# music_51.net
KiCad netlist of a schematic drawn in Altium Designer
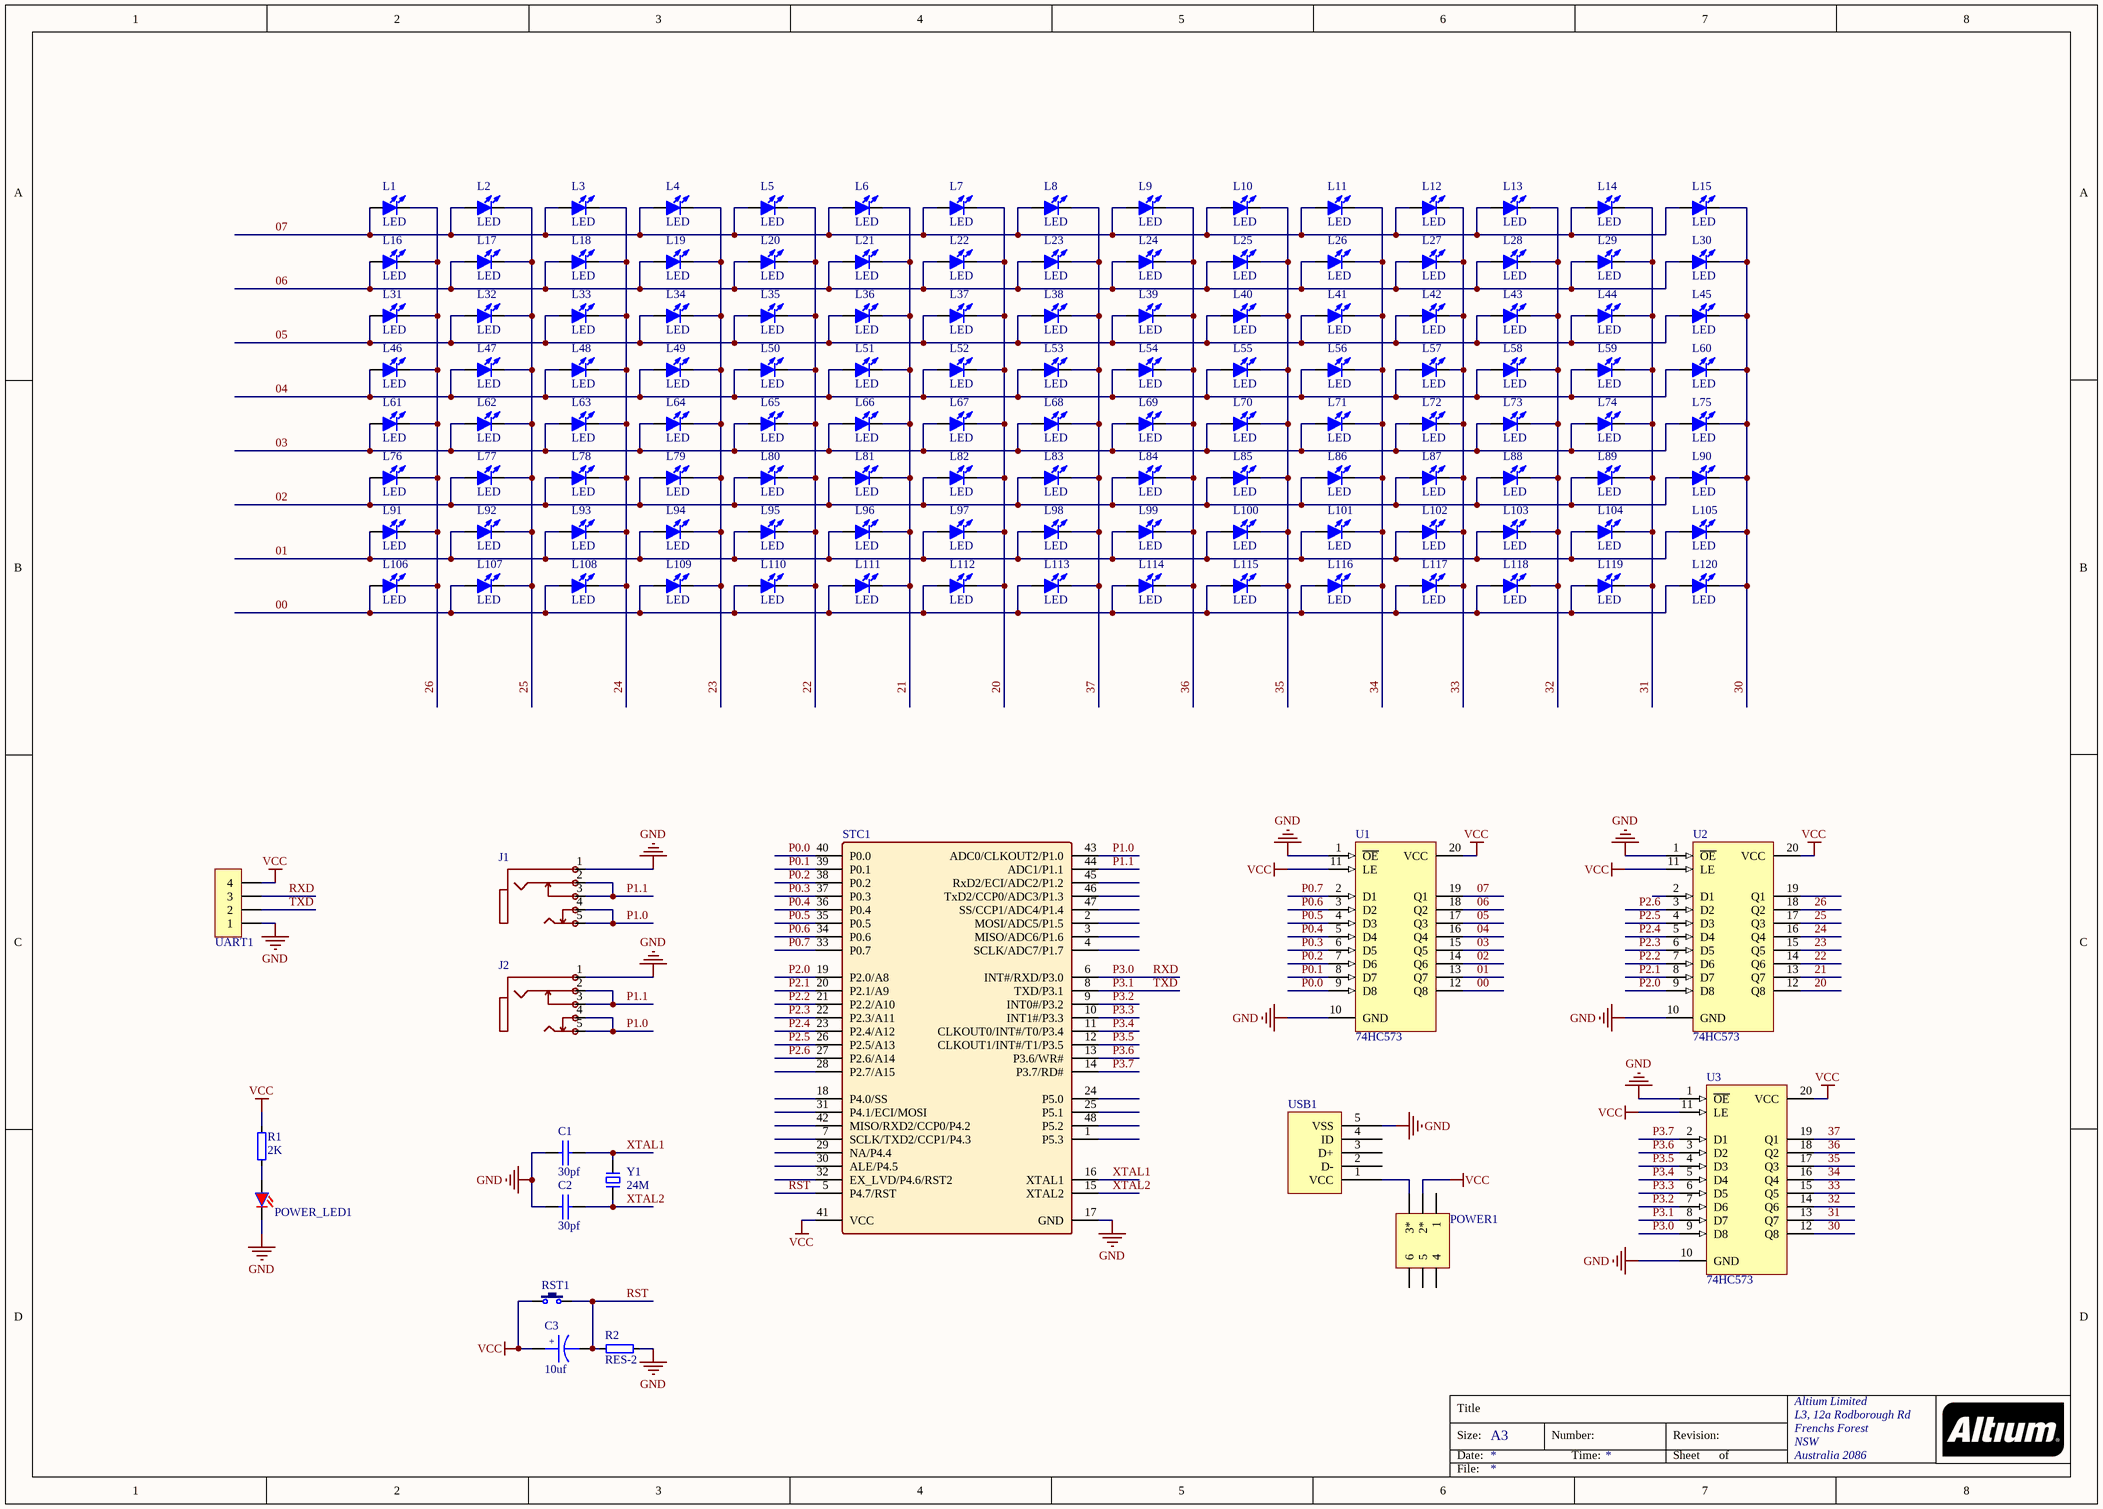
[diagram p0: music_51.SchDoc]

(export (version "E")
  (design (tool "Eeschema 10.0.6"))
  (components
    (comp (ref "C1") (value "30pf") (footprint "CAP-0805") (libsource (lib "Mylib_SCH") (part "Cap")))
    (comp (ref "C2") (value "30pf") (footprint "CAP-0805") (libsource (lib "Mylib_SCH") (part "Cap")))
    (comp (ref "C3") (value "10uf") (footprint "CAP-0805") (libsource (lib "Mylib_SCH") (part "Cap3+")))
    (comp (ref "J1") (value "PJ-307C") (footprint "PJ-307C") (libsource (lib "Mylib_SCH") (part "PJ-307C")))
    (comp (ref "J2") (value "PJ-307C") (footprint "PJ-307C") (libsource (lib "Mylib_SCH") (part "PJ-307C")))
    (comp (ref "L1") (value "LED") (footprint "LED") (libsource (lib "Mylib_SCH") (part "LED")))
    (comp (ref "L2") (value "LED") (footprint "LED") (libsource (lib "Mylib_SCH") (part "LED")))
    (comp (ref "L3") (value "LED") (footprint "LED") (libsource (lib "Mylib_SCH") (part "LED")))
    (comp (ref "L4") (value "LED") (footprint "LED") (libsource (lib "Mylib_SCH") (part "LED")))
    (comp (ref "L5") (value "LED") (footprint "LED") (libsource (lib "Mylib_SCH") (part "LED")))
    (comp (ref "L6") (value "LED") (footprint "LED") (libsource (lib "Mylib_SCH") (part "LED")))
    (comp (ref "L7") (value "LED") (footprint "LED") (libsource (lib "Mylib_SCH") (part "LED")))
    (comp (ref "L8") (value "LED") (footprint "LED") (libsource (lib "Mylib_SCH") (part "LED")))
    (comp (ref "L9") (value "LED") (footprint "LED") (libsource (lib "Mylib_SCH") (part "LED")))
    (comp (ref "L10") (value "LED") (footprint "LED") (libsource (lib "Mylib_SCH") (part "LED")))
    (comp (ref "L11") (value "LED") (footprint "LED") (libsource (lib "Mylib_SCH") (part "LED")))
    (comp (ref "L12") (value "LED") (footprint "LED") (libsource (lib "Mylib_SCH") (part "LED")))
    (comp (ref "L13") (value "LED") (footprint "LED") (libsource (lib "Mylib_SCH") (part "LED")))
    (comp (ref "L14") (value "LED") (footprint "LED") (libsource (lib "Mylib_SCH") (part "LED")))
    (comp (ref "L15") (value "LED") (footprint "LED") (libsource (lib "Mylib_SCH") (part "LED")))
    (comp (ref "L16") (value "LED") (footprint "LED") (libsource (lib "Mylib_SCH") (part "LED")))
    (comp (ref "L17") (value "LED") (footprint "LED") (libsource (lib "Mylib_SCH") (part "LED")))
    (comp (ref "L18") (value "LED") (footprint "LED") (libsource (lib "Mylib_SCH") (part "LED")))
    (comp (ref "L19") (value "LED") (footprint "LED") (libsource (lib "Mylib_SCH") (part "LED")))
    (comp (ref "L20") (value "LED") (footprint "LED") (libsource (lib "Mylib_SCH") (part "LED")))
    (comp (ref "L21") (value "LED") (footprint "LED") (libsource (lib "Mylib_SCH") (part "LED")))
    (comp (ref "L22") (value "LED") (footprint "LED") (libsource (lib "Mylib_SCH") (part "LED")))
    (comp (ref "L23") (value "LED") (footprint "LED") (libsource (lib "Mylib_SCH") (part "LED")))
    (comp (ref "L24") (value "LED") (footprint "LED") (libsource (lib "Mylib_SCH") (part "LED")))
    (comp (ref "L25") (value "LED") (footprint "LED") (libsource (lib "Mylib_SCH") (part "LED")))
    (comp (ref "L26") (value "LED") (footprint "LED") (libsource (lib "Mylib_SCH") (part "LED")))
    (comp (ref "L27") (value "LED") (footprint "LED") (libsource (lib "Mylib_SCH") (part "LED")))
    (comp (ref "L28") (value "LED") (footprint "LED") (libsource (lib "Mylib_SCH") (part "LED")))
    (comp (ref "L29") (value "LED") (footprint "LED") (libsource (lib "Mylib_SCH") (part "LED")))
    (comp (ref "L30") (value "LED") (footprint "LED") (libsource (lib "Mylib_SCH") (part "LED")))
    (comp (ref "L31") (value "LED") (footprint "LED") (libsource (lib "Mylib_SCH") (part "LED")))
    (comp (ref "L32") (value "LED") (footprint "LED") (libsource (lib "Mylib_SCH") (part "LED")))
    (comp (ref "L33") (value "LED") (footprint "LED") (libsource (lib "Mylib_SCH") (part "LED")))
    (comp (ref "L34") (value "LED") (footprint "LED") (libsource (lib "Mylib_SCH") (part "LED")))
    (comp (ref "L35") (value "LED") (footprint "LED") (libsource (lib "Mylib_SCH") (part "LED")))
    (comp (ref "L36") (value "LED") (footprint "LED") (libsource (lib "Mylib_SCH") (part "LED")))
    (comp (ref "L37") (value "LED") (footprint "LED") (libsource (lib "Mylib_SCH") (part "LED")))
    (comp (ref "L38") (value "LED") (footprint "LED") (libsource (lib "Mylib_SCH") (part "LED")))
    (comp (ref "L39") (value "LED") (footprint "LED") (libsource (lib "Mylib_SCH") (part "LED")))
    (comp (ref "L40") (value "LED") (footprint "LED") (libsource (lib "Mylib_SCH") (part "LED")))
    (comp (ref "L41") (value "LED") (footprint "LED") (libsource (lib "Mylib_SCH") (part "LED")))
    (comp (ref "L42") (value "LED") (footprint "LED") (libsource (lib "Mylib_SCH") (part "LED")))
    (comp (ref "L43") (value "LED") (footprint "LED") (libsource (lib "Mylib_SCH") (part "LED")))
    (comp (ref "L44") (value "LED") (footprint "LED") (libsource (lib "Mylib_SCH") (part "LED")))
    (comp (ref "L45") (value "LED") (footprint "LED") (libsource (lib "Mylib_SCH") (part "LED")))
    (comp (ref "L46") (value "LED") (footprint "LED") (libsource (lib "Mylib_SCH") (part "LED")))
    (comp (ref "L47") (value "LED") (footprint "LED") (libsource (lib "Mylib_SCH") (part "LED")))
    (comp (ref "L48") (value "LED") (footprint "LED") (libsource (lib "Mylib_SCH") (part "LED")))
    (comp (ref "L49") (value "LED") (footprint "LED") (libsource (lib "Mylib_SCH") (part "LED")))
    (comp (ref "L50") (value "LED") (footprint "LED") (libsource (lib "Mylib_SCH") (part "LED")))
    (comp (ref "L51") (value "LED") (footprint "LED") (libsource (lib "Mylib_SCH") (part "LED")))
    (comp (ref "L52") (value "LED") (footprint "LED") (libsource (lib "Mylib_SCH") (part "LED")))
    (comp (ref "L53") (value "LED") (footprint "LED") (libsource (lib "Mylib_SCH") (part "LED")))
    (comp (ref "L54") (value "LED") (footprint "LED") (libsource (lib "Mylib_SCH") (part "LED")))
    (comp (ref "L55") (value "LED") (footprint "LED") (libsource (lib "Mylib_SCH") (part "LED")))
    (comp (ref "L56") (value "LED") (footprint "LED") (libsource (lib "Mylib_SCH") (part "LED")))
    (comp (ref "L57") (value "LED") (footprint "LED") (libsource (lib "Mylib_SCH") (part "LED")))
    (comp (ref "L58") (value "LED") (footprint "LED") (libsource (lib "Mylib_SCH") (part "LED")))
    (comp (ref "L59") (value "LED") (footprint "LED") (libsource (lib "Mylib_SCH") (part "LED")))
    (comp (ref "L60") (value "LED") (footprint "LED") (libsource (lib "Mylib_SCH") (part "LED")))
    (comp (ref "L61") (value "LED") (footprint "LED") (libsource (lib "Mylib_SCH") (part "LED")))
    (comp (ref "L62") (value "LED") (footprint "LED") (libsource (lib "Mylib_SCH") (part "LED")))
    (comp (ref "L63") (value "LED") (footprint "LED") (libsource (lib "Mylib_SCH") (part "LED")))
    (comp (ref "L64") (value "LED") (footprint "LED") (libsource (lib "Mylib_SCH") (part "LED")))
    (comp (ref "L65") (value "LED") (footprint "LED") (libsource (lib "Mylib_SCH") (part "LED")))
    (comp (ref "L66") (value "LED") (footprint "LED") (libsource (lib "Mylib_SCH") (part "LED")))
    (comp (ref "L67") (value "LED") (footprint "LED") (libsource (lib "Mylib_SCH") (part "LED")))
    (comp (ref "L68") (value "LED") (footprint "LED") (libsource (lib "Mylib_SCH") (part "LED")))
    (comp (ref "L69") (value "LED") (footprint "LED") (libsource (lib "Mylib_SCH") (part "LED")))
    (comp (ref "L70") (value "LED") (footprint "LED") (libsource (lib "Mylib_SCH") (part "LED")))
    (comp (ref "L71") (value "LED") (footprint "LED") (libsource (lib "Mylib_SCH") (part "LED")))
    (comp (ref "L72") (value "LED") (footprint "LED") (libsource (lib "Mylib_SCH") (part "LED")))
    (comp (ref "L73") (value "LED") (footprint "LED") (libsource (lib "Mylib_SCH") (part "LED")))
    (comp (ref "L74") (value "LED") (footprint "LED") (libsource (lib "Mylib_SCH") (part "LED")))
    (comp (ref "L75") (value "LED") (footprint "LED") (libsource (lib "Mylib_SCH") (part "LED")))
    (comp (ref "L76") (value "LED") (footprint "LED") (libsource (lib "Mylib_SCH") (part "LED")))
    (comp (ref "L77") (value "LED") (footprint "LED") (libsource (lib "Mylib_SCH") (part "LED")))
    (comp (ref "L78") (value "LED") (footprint "LED") (libsource (lib "Mylib_SCH") (part "LED")))
    (comp (ref "L79") (value "LED") (footprint "LED") (libsource (lib "Mylib_SCH") (part "LED")))
    (comp (ref "L80") (value "LED") (footprint "LED") (libsource (lib "Mylib_SCH") (part "LED")))
    (comp (ref "L81") (value "LED") (footprint "LED") (libsource (lib "Mylib_SCH") (part "LED")))
    (comp (ref "L82") (value "LED") (footprint "LED") (libsource (lib "Mylib_SCH") (part "LED")))
    (comp (ref "L83") (value "LED") (footprint "LED") (libsource (lib "Mylib_SCH") (part "LED")))
    (comp (ref "L84") (value "LED") (footprint "LED") (libsource (lib "Mylib_SCH") (part "LED")))
    (comp (ref "L85") (value "LED") (footprint "LED") (libsource (lib "Mylib_SCH") (part "LED")))
    (comp (ref "L86") (value "LED") (footprint "LED") (libsource (lib "Mylib_SCH") (part "LED")))
    (comp (ref "L87") (value "LED") (footprint "LED") (libsource (lib "Mylib_SCH") (part "LED")))
    (comp (ref "L88") (value "LED") (footprint "LED") (libsource (lib "Mylib_SCH") (part "LED")))
    (comp (ref "L89") (value "LED") (footprint "LED") (libsource (lib "Mylib_SCH") (part "LED")))
    (comp (ref "L90") (value "LED") (footprint "LED") (libsource (lib "Mylib_SCH") (part "LED")))
    (comp (ref "L91") (value "LED") (footprint "LED") (libsource (lib "Mylib_SCH") (part "LED")))
    (comp (ref "L92") (value "LED") (footprint "LED") (libsource (lib "Mylib_SCH") (part "LED")))
    (comp (ref "L93") (value "LED") (footprint "LED") (libsource (lib "Mylib_SCH") (part "LED")))
    (comp (ref "L94") (value "LED") (footprint "LED") (libsource (lib "Mylib_SCH") (part "LED")))
    (comp (ref "L95") (value "LED") (footprint "LED") (libsource (lib "Mylib_SCH") (part "LED")))
    (comp (ref "L96") (value "LED") (footprint "LED") (libsource (lib "Mylib_SCH") (part "LED")))
    (comp (ref "L97") (value "LED") (footprint "LED") (libsource (lib "Mylib_SCH") (part "LED")))
    (comp (ref "L98") (value "LED") (footprint "LED") (libsource (lib "Mylib_SCH") (part "LED")))
    (comp (ref "L99") (value "LED") (footprint "LED") (libsource (lib "Mylib_SCH") (part "LED")))
    (comp (ref "L100") (value "LED") (footprint "LED") (libsource (lib "Mylib_SCH") (part "LED")))
    (comp (ref "L101") (value "LED") (footprint "LED") (libsource (lib "Mylib_SCH") (part "LED")))
    (comp (ref "L102") (value "LED") (footprint "LED") (libsource (lib "Mylib_SCH") (part "LED")))
    (comp (ref "L103") (value "LED") (footprint "LED") (libsource (lib "Mylib_SCH") (part "LED")))
    (comp (ref "L104") (value "LED") (footprint "LED") (libsource (lib "Mylib_SCH") (part "LED")))
    (comp (ref "L105") (value "LED") (footprint "LED") (libsource (lib "Mylib_SCH") (part "LED")))
    (comp (ref "L106") (value "LED") (footprint "LED") (libsource (lib "Mylib_SCH") (part "LED")))
    (comp (ref "L107") (value "LED") (footprint "LED") (libsource (lib "Mylib_SCH") (part "LED")))
    (comp (ref "L108") (value "LED") (footprint "LED") (libsource (lib "Mylib_SCH") (part "LED")))
    (comp (ref "L109") (value "LED") (footprint "LED") (libsource (lib "Mylib_SCH") (part "LED")))
    (comp (ref "L110") (value "LED") (footprint "LED") (libsource (lib "Mylib_SCH") (part "LED")))
    (comp (ref "L111") (value "LED") (footprint "LED") (libsource (lib "Mylib_SCH") (part "LED")))
    (comp (ref "L112") (value "LED") (footprint "LED") (libsource (lib "Mylib_SCH") (part "LED")))
    (comp (ref "L113") (value "LED") (footprint "LED") (libsource (lib "Mylib_SCH") (part "LED")))
    (comp (ref "L114") (value "LED") (footprint "LED") (libsource (lib "Mylib_SCH") (part "LED")))
    (comp (ref "L115") (value "LED") (footprint "LED") (libsource (lib "Mylib_SCH") (part "LED")))
    (comp (ref "L116") (value "LED") (footprint "LED") (libsource (lib "Mylib_SCH") (part "LED")))
    (comp (ref "L117") (value "LED") (footprint "LED") (libsource (lib "Mylib_SCH") (part "LED")))
    (comp (ref "L118") (value "LED") (footprint "LED") (libsource (lib "Mylib_SCH") (part "LED")))
    (comp (ref "L119") (value "LED") (footprint "LED") (libsource (lib "Mylib_SCH") (part "LED")))
    (comp (ref "L120") (value "LED") (footprint "LED") (libsource (lib "Mylib_SCH") (part "LED")))
    (comp (ref "POWER1") (value "SWITCH") (footprint "KEY6") (libsource (lib "My51Lib") (part "SWITCH")))
    (comp (ref "POWER_LED1")
      (value "LED_Red")
      (footprint "LED")
      (libsource (lib "Mylib_SCH") (part "LED_Red"))
    )
    (comp (ref "R1") (value "2K") (footprint "RES-S0805") (libsource (lib "Mylib_SCH") (part "RES-2")))
    (comp (ref "R2") (value "RES-2") (footprint "RES-S0805") (libsource (lib "Mylib_SCH") (part "RES-2")))
    (comp (ref "RST1") (value "Key") (footprint "KEY4") (libsource (lib "Mylib_SCH") (part "Key")))
    (comp (ref "STC1")
      (value "STC12C5A60S2")
      (footprint "LQPF48_7*7")
      (libsource (lib "Mylib_SCH") (part "STC12C5A60S2"))
    )
    (comp (ref "U1") (value "74HC573") (footprint "SOIC-20") (libsource (lib "Mylib_SCH") (part "74HC573")))
    (comp (ref "U2") (value "74HC573") (footprint "SOIC-20") (libsource (lib "Mylib_SCH") (part "74HC573")))
    (comp (ref "U3") (value "74HC573") (footprint "SOIC-20") (libsource (lib "Mylib_SCH") (part "74HC573")))
    (comp (ref "UART1")
      (value "Header 1*4")
      (footprint "Header 1*4")
      (libsource (lib "Mylib_SCH") (part "Header 1*4"))
    )
    (comp (ref "USB1") (value "USB_M") (footprint "MICRO_USB") (libsource (lib "Mylib_SCH") (part "USB_M")))
    (comp (ref "Y1") (value "24M") (footprint "XTAL") (libsource (lib "Mylib_SCH") (part "晶振")))
  )
  (nets
    (net (code "1") (name "/00") (class "Default")
      (node (ref "L106") (pin "1") (pinfunction "A_1") (pintype "passive"))
      (node (ref "L107") (pin "1") (pinfunction "A_1") (pintype "passive"))
      (node (ref "L108") (pin "1") (pinfunction "A_1") (pintype "passive"))
      (node (ref "L109") (pin "1") (pinfunction "A_1") (pintype "passive"))
      (node (ref "L110") (pin "1") (pinfunction "A_1") (pintype "passive"))
      (node (ref "L111") (pin "1") (pinfunction "A_1") (pintype "passive"))
      (node (ref "L112") (pin "1") (pinfunction "A_1") (pintype "passive"))
      (node (ref "L113") (pin "1") (pinfunction "A_1") (pintype "passive"))
      (node (ref "L114") (pin "1") (pinfunction "A_1") (pintype "passive"))
      (node (ref "L115") (pin "1") (pinfunction "A_1") (pintype "passive"))
      (node (ref "L116") (pin "1") (pinfunction "A_1") (pintype "passive"))
      (node (ref "L117") (pin "1") (pinfunction "A_1") (pintype "passive"))
      (node (ref "L118") (pin "1") (pinfunction "A_1") (pintype "passive"))
      (node (ref "L119") (pin "1") (pinfunction "A_1") (pintype "passive"))
      (node (ref "L120") (pin "1") (pinfunction "A_1") (pintype "passive"))
      (node (ref "U1") (pin "12") (pinfunction "Q8_12") (pintype "tri_state"))
    )
    (net (code "2") (name "/01") (class "Default")
      (node (ref "L100") (pin "1") (pinfunction "A_1") (pintype "passive"))
      (node (ref "L101") (pin "1") (pinfunction "A_1") (pintype "passive"))
      (node (ref "L102") (pin "1") (pinfunction "A_1") (pintype "passive"))
      (node (ref "L103") (pin "1") (pinfunction "A_1") (pintype "passive"))
      (node (ref "L104") (pin "1") (pinfunction "A_1") (pintype "passive"))
      (node (ref "L105") (pin "1") (pinfunction "A_1") (pintype "passive"))
      (node (ref "L91") (pin "1") (pinfunction "A_1") (pintype "passive"))
      (node (ref "L92") (pin "1") (pinfunction "A_1") (pintype "passive"))
      (node (ref "L93") (pin "1") (pinfunction "A_1") (pintype "passive"))
      (node (ref "L94") (pin "1") (pinfunction "A_1") (pintype "passive"))
      (node (ref "L95") (pin "1") (pinfunction "A_1") (pintype "passive"))
      (node (ref "L96") (pin "1") (pinfunction "A_1") (pintype "passive"))
      (node (ref "L97") (pin "1") (pinfunction "A_1") (pintype "passive"))
      (node (ref "L98") (pin "1") (pinfunction "A_1") (pintype "passive"))
      (node (ref "L99") (pin "1") (pinfunction "A_1") (pintype "passive"))
      (node (ref "U1") (pin "13") (pinfunction "Q7_13") (pintype "tri_state"))
    )
    (net (code "3") (name "/02") (class "Default")
      (node (ref "L76") (pin "1") (pinfunction "A_1") (pintype "passive"))
      (node (ref "L77") (pin "1") (pinfunction "A_1") (pintype "passive"))
      (node (ref "L78") (pin "1") (pinfunction "A_1") (pintype "passive"))
      (node (ref "L79") (pin "1") (pinfunction "A_1") (pintype "passive"))
      (node (ref "L80") (pin "1") (pinfunction "A_1") (pintype "passive"))
      (node (ref "L81") (pin "1") (pinfunction "A_1") (pintype "passive"))
      (node (ref "L82") (pin "1") (pinfunction "A_1") (pintype "passive"))
      (node (ref "L83") (pin "1") (pinfunction "A_1") (pintype "passive"))
      (node (ref "L84") (pin "1") (pinfunction "A_1") (pintype "passive"))
      (node (ref "L85") (pin "1") (pinfunction "A_1") (pintype "passive"))
      (node (ref "L86") (pin "1") (pinfunction "A_1") (pintype "passive"))
      (node (ref "L87") (pin "1") (pinfunction "A_1") (pintype "passive"))
      (node (ref "L88") (pin "1") (pinfunction "A_1") (pintype "passive"))
      (node (ref "L89") (pin "1") (pinfunction "A_1") (pintype "passive"))
      (node (ref "L90") (pin "1") (pinfunction "A_1") (pintype "passive"))
      (node (ref "U1") (pin "14") (pinfunction "Q6_14") (pintype "tri_state"))
    )
    (net (code "4") (name "/03") (class "Default")
      (node (ref "L61") (pin "1") (pinfunction "A_1") (pintype "passive"))
      (node (ref "L62") (pin "1") (pinfunction "A_1") (pintype "passive"))
      (node (ref "L63") (pin "1") (pinfunction "A_1") (pintype "passive"))
      (node (ref "L64") (pin "1") (pinfunction "A_1") (pintype "passive"))
      (node (ref "L65") (pin "1") (pinfunction "A_1") (pintype "passive"))
      (node (ref "L66") (pin "1") (pinfunction "A_1") (pintype "passive"))
      (node (ref "L67") (pin "1") (pinfunction "A_1") (pintype "passive"))
      (node (ref "L68") (pin "1") (pinfunction "A_1") (pintype "passive"))
      (node (ref "L69") (pin "1") (pinfunction "A_1") (pintype "passive"))
      (node (ref "L70") (pin "1") (pinfunction "A_1") (pintype "passive"))
      (node (ref "L71") (pin "1") (pinfunction "A_1") (pintype "passive"))
      (node (ref "L72") (pin "1") (pinfunction "A_1") (pintype "passive"))
      (node (ref "L73") (pin "1") (pinfunction "A_1") (pintype "passive"))
      (node (ref "L74") (pin "1") (pinfunction "A_1") (pintype "passive"))
      (node (ref "L75") (pin "1") (pinfunction "A_1") (pintype "passive"))
      (node (ref "U1") (pin "15") (pinfunction "Q5_15") (pintype "tri_state"))
    )
    (net (code "5") (name "/04") (class "Default")
      (node (ref "L46") (pin "1") (pinfunction "A_1") (pintype "passive"))
      (node (ref "L47") (pin "1") (pinfunction "A_1") (pintype "passive"))
      (node (ref "L48") (pin "1") (pinfunction "A_1") (pintype "passive"))
      (node (ref "L49") (pin "1") (pinfunction "A_1") (pintype "passive"))
      (node (ref "L50") (pin "1") (pinfunction "A_1") (pintype "passive"))
      (node (ref "L51") (pin "1") (pinfunction "A_1") (pintype "passive"))
      (node (ref "L52") (pin "1") (pinfunction "A_1") (pintype "passive"))
      (node (ref "L53") (pin "1") (pinfunction "A_1") (pintype "passive"))
      (node (ref "L54") (pin "1") (pinfunction "A_1") (pintype "passive"))
      (node (ref "L55") (pin "1") (pinfunction "A_1") (pintype "passive"))
      (node (ref "L56") (pin "1") (pinfunction "A_1") (pintype "passive"))
      (node (ref "L57") (pin "1") (pinfunction "A_1") (pintype "passive"))
      (node (ref "L58") (pin "1") (pinfunction "A_1") (pintype "passive"))
      (node (ref "L59") (pin "1") (pinfunction "A_1") (pintype "passive"))
      (node (ref "L60") (pin "1") (pinfunction "A_1") (pintype "passive"))
      (node (ref "U1") (pin "16") (pinfunction "Q4_16") (pintype "tri_state"))
    )
    (net (code "6") (name "/05") (class "Default")
      (node (ref "L31") (pin "1") (pinfunction "A_1") (pintype "passive"))
      (node (ref "L32") (pin "1") (pinfunction "A_1") (pintype "passive"))
      (node (ref "L33") (pin "1") (pinfunction "A_1") (pintype "passive"))
      (node (ref "L34") (pin "1") (pinfunction "A_1") (pintype "passive"))
      (node (ref "L35") (pin "1") (pinfunction "A_1") (pintype "passive"))
      (node (ref "L36") (pin "1") (pinfunction "A_1") (pintype "passive"))
      (node (ref "L37") (pin "1") (pinfunction "A_1") (pintype "passive"))
      (node (ref "L38") (pin "1") (pinfunction "A_1") (pintype "passive"))
      (node (ref "L39") (pin "1") (pinfunction "A_1") (pintype "passive"))
      (node (ref "L40") (pin "1") (pinfunction "A_1") (pintype "passive"))
      (node (ref "L41") (pin "1") (pinfunction "A_1") (pintype "passive"))
      (node (ref "L42") (pin "1") (pinfunction "A_1") (pintype "passive"))
      (node (ref "L43") (pin "1") (pinfunction "A_1") (pintype "passive"))
      (node (ref "L44") (pin "1") (pinfunction "A_1") (pintype "passive"))
      (node (ref "L45") (pin "1") (pinfunction "A_1") (pintype "passive"))
      (node (ref "U1") (pin "17") (pinfunction "Q3_17") (pintype "tri_state"))
    )
    (net (code "7") (name "/06") (class "Default")
      (node (ref "L16") (pin "1") (pinfunction "A_1") (pintype "passive"))
      (node (ref "L17") (pin "1") (pinfunction "A_1") (pintype "passive"))
      (node (ref "L18") (pin "1") (pinfunction "A_1") (pintype "passive"))
      (node (ref "L19") (pin "1") (pinfunction "A_1") (pintype "passive"))
      (node (ref "L20") (pin "1") (pinfunction "A_1") (pintype "passive"))
      (node (ref "L21") (pin "1") (pinfunction "A_1") (pintype "passive"))
      (node (ref "L22") (pin "1") (pinfunction "A_1") (pintype "passive"))
      (node (ref "L23") (pin "1") (pinfunction "A_1") (pintype "passive"))
      (node (ref "L24") (pin "1") (pinfunction "A_1") (pintype "passive"))
      (node (ref "L25") (pin "1") (pinfunction "A_1") (pintype "passive"))
      (node (ref "L26") (pin "1") (pinfunction "A_1") (pintype "passive"))
      (node (ref "L27") (pin "1") (pinfunction "A_1") (pintype "passive"))
      (node (ref "L28") (pin "1") (pinfunction "A_1") (pintype "passive"))
      (node (ref "L29") (pin "1") (pinfunction "A_1") (pintype "passive"))
      (node (ref "L30") (pin "1") (pinfunction "A_1") (pintype "passive"))
      (node (ref "U1") (pin "18") (pinfunction "Q2_18") (pintype "tri_state"))
    )
    (net (code "8") (name "/07") (class "Default")
      (node (ref "L1") (pin "1") (pinfunction "A_1") (pintype "passive"))
      (node (ref "L10") (pin "1") (pinfunction "A_1") (pintype "passive"))
      (node (ref "L11") (pin "1") (pinfunction "A_1") (pintype "passive"))
      (node (ref "L12") (pin "1") (pinfunction "A_1") (pintype "passive"))
      (node (ref "L13") (pin "1") (pinfunction "A_1") (pintype "passive"))
      (node (ref "L14") (pin "1") (pinfunction "A_1") (pintype "passive"))
      (node (ref "L15") (pin "1") (pinfunction "A_1") (pintype "passive"))
      (node (ref "L2") (pin "1") (pinfunction "A_1") (pintype "passive"))
      (node (ref "L3") (pin "1") (pinfunction "A_1") (pintype "passive"))
      (node (ref "L4") (pin "1") (pinfunction "A_1") (pintype "passive"))
      (node (ref "L5") (pin "1") (pinfunction "A_1") (pintype "passive"))
      (node (ref "L6") (pin "1") (pinfunction "A_1") (pintype "passive"))
      (node (ref "L7") (pin "1") (pinfunction "A_1") (pintype "passive"))
      (node (ref "L8") (pin "1") (pinfunction "A_1") (pintype "passive"))
      (node (ref "L9") (pin "1") (pinfunction "A_1") (pintype "passive"))
      (node (ref "U1") (pin "19") (pinfunction "Q1_19") (pintype "tri_state"))
    )
    (net (code "9") (name "/20") (class "Default")
      (node (ref "L112") (pin "2") (pinfunction "K_2") (pintype "passive"))
      (node (ref "L22") (pin "2") (pinfunction "K_2") (pintype "passive"))
      (node (ref "L37") (pin "2") (pinfunction "K_2") (pintype "passive"))
      (node (ref "L52") (pin "2") (pinfunction "K_2") (pintype "passive"))
      (node (ref "L67") (pin "2") (pinfunction "K_2") (pintype "passive"))
      (node (ref "L7") (pin "2") (pinfunction "K_2") (pintype "passive"))
      (node (ref "L82") (pin "2") (pinfunction "K_2") (pintype "passive"))
      (node (ref "L97") (pin "2") (pinfunction "K_2") (pintype "passive"))
      (node (ref "U2") (pin "12") (pinfunction "Q8_12") (pintype "tri_state"))
    )
    (net (code "10") (name "/21") (class "Default")
      (node (ref "L111") (pin "2") (pinfunction "K_2") (pintype "passive"))
      (node (ref "L21") (pin "2") (pinfunction "K_2") (pintype "passive"))
      (node (ref "L36") (pin "2") (pinfunction "K_2") (pintype "passive"))
      (node (ref "L51") (pin "2") (pinfunction "K_2") (pintype "passive"))
      (node (ref "L6") (pin "2") (pinfunction "K_2") (pintype "passive"))
      (node (ref "L66") (pin "2") (pinfunction "K_2") (pintype "passive"))
      (node (ref "L81") (pin "2") (pinfunction "K_2") (pintype "passive"))
      (node (ref "L96") (pin "2") (pinfunction "K_2") (pintype "passive"))
      (node (ref "U2") (pin "13") (pinfunction "Q7_13") (pintype "tri_state"))
    )
    (net (code "11") (name "/22") (class "Default")
      (node (ref "L110") (pin "2") (pinfunction "K_2") (pintype "passive"))
      (node (ref "L20") (pin "2") (pinfunction "K_2") (pintype "passive"))
      (node (ref "L35") (pin "2") (pinfunction "K_2") (pintype "passive"))
      (node (ref "L5") (pin "2") (pinfunction "K_2") (pintype "passive"))
      (node (ref "L50") (pin "2") (pinfunction "K_2") (pintype "passive"))
      (node (ref "L65") (pin "2") (pinfunction "K_2") (pintype "passive"))
      (node (ref "L80") (pin "2") (pinfunction "K_2") (pintype "passive"))
      (node (ref "L95") (pin "2") (pinfunction "K_2") (pintype "passive"))
      (node (ref "U2") (pin "14") (pinfunction "Q6_14") (pintype "tri_state"))
    )
    (net (code "12") (name "/23") (class "Default")
      (node (ref "L109") (pin "2") (pinfunction "K_2") (pintype "passive"))
      (node (ref "L19") (pin "2") (pinfunction "K_2") (pintype "passive"))
      (node (ref "L34") (pin "2") (pinfunction "K_2") (pintype "passive"))
      (node (ref "L4") (pin "2") (pinfunction "K_2") (pintype "passive"))
      (node (ref "L49") (pin "2") (pinfunction "K_2") (pintype "passive"))
      (node (ref "L64") (pin "2") (pinfunction "K_2") (pintype "passive"))
      (node (ref "L79") (pin "2") (pinfunction "K_2") (pintype "passive"))
      (node (ref "L94") (pin "2") (pinfunction "K_2") (pintype "passive"))
      (node (ref "U2") (pin "15") (pinfunction "Q5_15") (pintype "tri_state"))
    )
    (net (code "13") (name "/24") (class "Default")
      (node (ref "L108") (pin "2") (pinfunction "K_2") (pintype "passive"))
      (node (ref "L18") (pin "2") (pinfunction "K_2") (pintype "passive"))
      (node (ref "L3") (pin "2") (pinfunction "K_2") (pintype "passive"))
      (node (ref "L33") (pin "2") (pinfunction "K_2") (pintype "passive"))
      (node (ref "L48") (pin "2") (pinfunction "K_2") (pintype "passive"))
      (node (ref "L63") (pin "2") (pinfunction "K_2") (pintype "passive"))
      (node (ref "L78") (pin "2") (pinfunction "K_2") (pintype "passive"))
      (node (ref "L93") (pin "2") (pinfunction "K_2") (pintype "passive"))
      (node (ref "U2") (pin "16") (pinfunction "Q4_16") (pintype "tri_state"))
    )
    (net (code "14") (name "/25") (class "Default")
      (node (ref "L107") (pin "2") (pinfunction "K_2") (pintype "passive"))
      (node (ref "L17") (pin "2") (pinfunction "K_2") (pintype "passive"))
      (node (ref "L2") (pin "2") (pinfunction "K_2") (pintype "passive"))
      (node (ref "L32") (pin "2") (pinfunction "K_2") (pintype "passive"))
      (node (ref "L47") (pin "2") (pinfunction "K_2") (pintype "passive"))
      (node (ref "L62") (pin "2") (pinfunction "K_2") (pintype "passive"))
      (node (ref "L77") (pin "2") (pinfunction "K_2") (pintype "passive"))
      (node (ref "L92") (pin "2") (pinfunction "K_2") (pintype "passive"))
      (node (ref "U2") (pin "17") (pinfunction "Q3_17") (pintype "tri_state"))
    )
    (net (code "15") (name "/26") (class "Default")
      (node (ref "L1") (pin "2") (pinfunction "K_2") (pintype "passive"))
      (node (ref "L106") (pin "2") (pinfunction "K_2") (pintype "passive"))
      (node (ref "L16") (pin "2") (pinfunction "K_2") (pintype "passive"))
      (node (ref "L31") (pin "2") (pinfunction "K_2") (pintype "passive"))
      (node (ref "L46") (pin "2") (pinfunction "K_2") (pintype "passive"))
      (node (ref "L61") (pin "2") (pinfunction "K_2") (pintype "passive"))
      (node (ref "L76") (pin "2") (pinfunction "K_2") (pintype "passive"))
      (node (ref "L91") (pin "2") (pinfunction "K_2") (pintype "passive"))
      (node (ref "U2") (pin "18") (pinfunction "Q2_18") (pintype "tri_state"))
    )
    (net (code "16") (name "/30") (class "Default")
      (node (ref "L105") (pin "2") (pinfunction "K_2") (pintype "passive"))
      (node (ref "L120") (pin "2") (pinfunction "K_2") (pintype "passive"))
      (node (ref "L15") (pin "2") (pinfunction "K_2") (pintype "passive"))
      (node (ref "L30") (pin "2") (pinfunction "K_2") (pintype "passive"))
      (node (ref "L45") (pin "2") (pinfunction "K_2") (pintype "passive"))
      (node (ref "L60") (pin "2") (pinfunction "K_2") (pintype "passive"))
      (node (ref "L75") (pin "2") (pinfunction "K_2") (pintype "passive"))
      (node (ref "L90") (pin "2") (pinfunction "K_2") (pintype "passive"))
      (node (ref "U3") (pin "12") (pinfunction "Q8_12") (pintype "tri_state"))
    )
    (net (code "17") (name "/31") (class "Default")
      (node (ref "L104") (pin "2") (pinfunction "K_2") (pintype "passive"))
      (node (ref "L119") (pin "2") (pinfunction "K_2") (pintype "passive"))
      (node (ref "L14") (pin "2") (pinfunction "K_2") (pintype "passive"))
      (node (ref "L29") (pin "2") (pinfunction "K_2") (pintype "passive"))
      (node (ref "L44") (pin "2") (pinfunction "K_2") (pintype "passive"))
      (node (ref "L59") (pin "2") (pinfunction "K_2") (pintype "passive"))
      (node (ref "L74") (pin "2") (pinfunction "K_2") (pintype "passive"))
      (node (ref "L89") (pin "2") (pinfunction "K_2") (pintype "passive"))
      (node (ref "U3") (pin "13") (pinfunction "Q7_13") (pintype "tri_state"))
    )
    (net (code "18") (name "/32") (class "Default")
      (node (ref "L103") (pin "2") (pinfunction "K_2") (pintype "passive"))
      (node (ref "L118") (pin "2") (pinfunction "K_2") (pintype "passive"))
      (node (ref "L13") (pin "2") (pinfunction "K_2") (pintype "passive"))
      (node (ref "L28") (pin "2") (pinfunction "K_2") (pintype "passive"))
      (node (ref "L43") (pin "2") (pinfunction "K_2") (pintype "passive"))
      (node (ref "L58") (pin "2") (pinfunction "K_2") (pintype "passive"))
      (node (ref "L73") (pin "2") (pinfunction "K_2") (pintype "passive"))
      (node (ref "L88") (pin "2") (pinfunction "K_2") (pintype "passive"))
      (node (ref "U3") (pin "14") (pinfunction "Q6_14") (pintype "tri_state"))
    )
    (net (code "19") (name "/33") (class "Default")
      (node (ref "L102") (pin "2") (pinfunction "K_2") (pintype "passive"))
      (node (ref "L117") (pin "2") (pinfunction "K_2") (pintype "passive"))
      (node (ref "L12") (pin "2") (pinfunction "K_2") (pintype "passive"))
      (node (ref "L27") (pin "2") (pinfunction "K_2") (pintype "passive"))
      (node (ref "L42") (pin "2") (pinfunction "K_2") (pintype "passive"))
      (node (ref "L57") (pin "2") (pinfunction "K_2") (pintype "passive"))
      (node (ref "L72") (pin "2") (pinfunction "K_2") (pintype "passive"))
      (node (ref "L87") (pin "2") (pinfunction "K_2") (pintype "passive"))
      (node (ref "U3") (pin "15") (pinfunction "Q5_15") (pintype "tri_state"))
    )
    (net (code "20") (name "/34") (class "Default")
      (node (ref "L101") (pin "2") (pinfunction "K_2") (pintype "passive"))
      (node (ref "L11") (pin "2") (pinfunction "K_2") (pintype "passive"))
      (node (ref "L116") (pin "2") (pinfunction "K_2") (pintype "passive"))
      (node (ref "L26") (pin "2") (pinfunction "K_2") (pintype "passive"))
      (node (ref "L41") (pin "2") (pinfunction "K_2") (pintype "passive"))
      (node (ref "L56") (pin "2") (pinfunction "K_2") (pintype "passive"))
      (node (ref "L71") (pin "2") (pinfunction "K_2") (pintype "passive"))
      (node (ref "L86") (pin "2") (pinfunction "K_2") (pintype "passive"))
      (node (ref "U3") (pin "16") (pinfunction "Q4_16") (pintype "tri_state"))
    )
    (net (code "21") (name "/35") (class "Default")
      (node (ref "L10") (pin "2") (pinfunction "K_2") (pintype "passive"))
      (node (ref "L100") (pin "2") (pinfunction "K_2") (pintype "passive"))
      (node (ref "L115") (pin "2") (pinfunction "K_2") (pintype "passive"))
      (node (ref "L25") (pin "2") (pinfunction "K_2") (pintype "passive"))
      (node (ref "L40") (pin "2") (pinfunction "K_2") (pintype "passive"))
      (node (ref "L55") (pin "2") (pinfunction "K_2") (pintype "passive"))
      (node (ref "L70") (pin "2") (pinfunction "K_2") (pintype "passive"))
      (node (ref "L85") (pin "2") (pinfunction "K_2") (pintype "passive"))
      (node (ref "U3") (pin "17") (pinfunction "Q3_17") (pintype "tri_state"))
    )
    (net (code "22") (name "/36") (class "Default")
      (node (ref "L114") (pin "2") (pinfunction "K_2") (pintype "passive"))
      (node (ref "L24") (pin "2") (pinfunction "K_2") (pintype "passive"))
      (node (ref "L39") (pin "2") (pinfunction "K_2") (pintype "passive"))
      (node (ref "L54") (pin "2") (pinfunction "K_2") (pintype "passive"))
      (node (ref "L69") (pin "2") (pinfunction "K_2") (pintype "passive"))
      (node (ref "L84") (pin "2") (pinfunction "K_2") (pintype "passive"))
      (node (ref "L9") (pin "2") (pinfunction "K_2") (pintype "passive"))
      (node (ref "L99") (pin "2") (pinfunction "K_2") (pintype "passive"))
      (node (ref "U3") (pin "18") (pinfunction "Q2_18") (pintype "tri_state"))
    )
    (net (code "23") (name "/37") (class "Default")
      (node (ref "L113") (pin "2") (pinfunction "K_2") (pintype "passive"))
      (node (ref "L23") (pin "2") (pinfunction "K_2") (pintype "passive"))
      (node (ref "L38") (pin "2") (pinfunction "K_2") (pintype "passive"))
      (node (ref "L53") (pin "2") (pinfunction "K_2") (pintype "passive"))
      (node (ref "L68") (pin "2") (pinfunction "K_2") (pintype "passive"))
      (node (ref "L8") (pin "2") (pinfunction "K_2") (pintype "passive"))
      (node (ref "L83") (pin "2") (pinfunction "K_2") (pintype "passive"))
      (node (ref "L98") (pin "2") (pinfunction "K_2") (pintype "passive"))
      (node (ref "U3") (pin "19") (pinfunction "Q1_19") (pintype "tri_state"))
    )
    (net (code "24") (name "/P0.0") (class "Default")
      (node (ref "STC1") (pin "40") (pinfunction "P0.0_40") (pintype "passive"))
      (node (ref "U1") (pin "9") (pinfunction "D8_9") (pintype "input"))
    )
    (net (code "25") (name "/P0.1") (class "Default")
      (node (ref "STC1") (pin "39") (pinfunction "P0.1_39") (pintype "passive"))
      (node (ref "U1") (pin "8") (pinfunction "D7_8") (pintype "input"))
    )
    (net (code "26") (name "/P0.2") (class "Default")
      (node (ref "STC1") (pin "38") (pinfunction "P0.2_38") (pintype "passive"))
      (node (ref "U1") (pin "7") (pinfunction "D6_7") (pintype "input"))
    )
    (net (code "27") (name "/P0.3") (class "Default")
      (node (ref "STC1") (pin "37") (pinfunction "P0.3_37") (pintype "passive"))
      (node (ref "U1") (pin "6") (pinfunction "D5_6") (pintype "input"))
    )
    (net (code "28") (name "/P0.4") (class "Default")
      (node (ref "STC1") (pin "36") (pinfunction "P0.4_36") (pintype "passive"))
      (node (ref "U1") (pin "5") (pinfunction "D4_5") (pintype "input"))
    )
    (net (code "29") (name "/P0.5") (class "Default")
      (node (ref "STC1") (pin "35") (pinfunction "P0.5_35") (pintype "passive"))
      (node (ref "U1") (pin "4") (pinfunction "D3_4") (pintype "input"))
    )
    (net (code "30") (name "/P0.6") (class "Default")
      (node (ref "STC1") (pin "34") (pinfunction "P0.6_34") (pintype "passive"))
      (node (ref "U1") (pin "3") (pinfunction "D2_3") (pintype "input"))
    )
    (net (code "31") (name "/P0.7") (class "Default")
      (node (ref "STC1") (pin "33") (pinfunction "P0.7_33") (pintype "passive"))
      (node (ref "U1") (pin "2") (pinfunction "D1_2") (pintype "input"))
    )
    (net (code "32") (name "/P1.0") (class "Default")
      (node (ref "J1") (pin "4") (pinfunction "4_4") (pintype "passive"))
      (node (ref "J1") (pin "5") (pinfunction "5_5") (pintype "passive"))
      (node (ref "J2") (pin "4") (pinfunction "4_4") (pintype "passive"))
      (node (ref "J2") (pin "5") (pinfunction "5_5") (pintype "passive"))
      (node (ref "STC1") (pin "43") (pinfunction "ADC0/CLKOUT2/P1.0_43") (pintype "passive"))
    )
    (net (code "33") (name "/P1.1") (class "Default")
      (node (ref "J1") (pin "2") (pinfunction "2_2") (pintype "passive"))
      (node (ref "J1") (pin "3") (pinfunction "3_3") (pintype "passive"))
      (node (ref "J2") (pin "2") (pinfunction "2_2") (pintype "passive"))
      (node (ref "J2") (pin "3") (pinfunction "3_3") (pintype "passive"))
      (node (ref "STC1") (pin "44") (pinfunction "ADC1/P1.1_44") (pintype "passive"))
    )
    (net (code "34") (name "/P2.0") (class "Default")
      (node (ref "STC1") (pin "19") (pinfunction "P2.0/A8_19") (pintype "passive"))
      (node (ref "U2") (pin "9") (pinfunction "D8_9") (pintype "input"))
    )
    (net (code "35") (name "/P2.1") (class "Default")
      (node (ref "STC1") (pin "20") (pinfunction "P2.1/A9_20") (pintype "passive"))
      (node (ref "U2") (pin "8") (pinfunction "D7_8") (pintype "input"))
    )
    (net (code "36") (name "/P2.2") (class "Default")
      (node (ref "STC1") (pin "21") (pinfunction "P2.2/A10_21") (pintype "passive"))
      (node (ref "U2") (pin "7") (pinfunction "D6_7") (pintype "input"))
    )
    (net (code "37") (name "/P2.3") (class "Default")
      (node (ref "STC1") (pin "22") (pinfunction "P2.3/A11_22") (pintype "passive"))
      (node (ref "U2") (pin "6") (pinfunction "D5_6") (pintype "input"))
    )
    (net (code "38") (name "/P2.4") (class "Default")
      (node (ref "STC1") (pin "23") (pinfunction "P2.4/A12_23") (pintype "passive"))
      (node (ref "U2") (pin "5") (pinfunction "D4_5") (pintype "input"))
    )
    (net (code "39") (name "/P2.5") (class "Default")
      (node (ref "STC1") (pin "26") (pinfunction "P2.5/A13_26") (pintype "passive"))
      (node (ref "U2") (pin "4") (pinfunction "D3_4") (pintype "input"))
    )
    (net (code "40") (name "/P2.6") (class "Default")
      (node (ref "STC1") (pin "27") (pinfunction "P2.6/A14_27") (pintype "passive"))
      (node (ref "U2") (pin "3") (pinfunction "D2_3") (pintype "input"))
    )
    (net (code "41") (name "/P3.0") (class "Default")
      (node (ref "STC1") (pin "6") (pinfunction "INT#/RXD/P3.0_6") (pintype "passive"))
      (node (ref "U3") (pin "9") (pinfunction "D8_9") (pintype "input"))
      (node (ref "UART1") (pin "3") (pinfunction "3_3") (pintype "passive"))
    )
    (net (code "42") (name "/P3.1") (class "Default")
      (node (ref "STC1") (pin "8") (pinfunction "TXD/P3.1_8") (pintype "passive"))
      (node (ref "U3") (pin "8") (pinfunction "D7_8") (pintype "input"))
      (node (ref "UART1") (pin "2") (pinfunction "2_2") (pintype "passive"))
    )
    (net (code "43") (name "/P3.2") (class "Default")
      (node (ref "STC1") (pin "9") (pinfunction "INT0#/P3.2_9") (pintype "passive"))
      (node (ref "U3") (pin "7") (pinfunction "D6_7") (pintype "input"))
    )
    (net (code "44") (name "/P3.3") (class "Default")
      (node (ref "STC1") (pin "10") (pinfunction "INT1#/P3.3_10") (pintype "passive"))
      (node (ref "U3") (pin "6") (pinfunction "D5_6") (pintype "input"))
    )
    (net (code "45") (name "/P3.4") (class "Default")
      (node (ref "STC1") (pin "11") (pinfunction "CLKOUT0/INT#/T0/P3.4_11") (pintype "passive"))
      (node (ref "U3") (pin "5") (pinfunction "D4_5") (pintype "input"))
    )
    (net (code "46") (name "/P3.5") (class "Default")
      (node (ref "STC1") (pin "12") (pinfunction "CLKOUT1/INT#/T1/P3.5_12") (pintype "passive"))
      (node (ref "U3") (pin "4") (pinfunction "D3_4") (pintype "input"))
    )
    (net (code "47") (name "/P3.6") (class "Default")
      (node (ref "STC1") (pin "13") (pinfunction "P3.6/WR#_13") (pintype "passive"))
      (node (ref "U3") (pin "3") (pinfunction "D2_3") (pintype "input"))
    )
    (net (code "48") (name "/P3.7") (class "Default")
      (node (ref "STC1") (pin "14") (pinfunction "P3.7/RD#_14") (pintype "passive"))
      (node (ref "U3") (pin "2") (pinfunction "D1_2") (pintype "input"))
    )
    (net (code "49") (name "/RST") (class "Default")
      (node (ref "C3") (pin "2") (pinfunction "2_2") (pintype "passive"))
      (node (ref "R2") (pin "1") (pinfunction "1_1") (pintype "passive"))
      (node (ref "RST1") (pin "2") (pinfunction "2_2") (pintype "passive"))
      (node (ref "STC1") (pin "5") (pinfunction "P4.7/RST_5") (pintype "passive"))
    )
    (net (code "50") (name "/XTAL1") (class "Default")
      (node (ref "C1") (pin "1") (pinfunction "1_1") (pintype "passive"))
      (node (ref "STC1") (pin "16") (pinfunction "XTAL1_16") (pintype "passive"))
      (node (ref "Y1") (pin "2") (pinfunction "2_2") (pintype "passive"))
    )
    (net (code "51") (name "/XTAL2") (class "Default")
      (node (ref "C2") (pin "2") (pinfunction "2_2") (pintype "passive"))
      (node (ref "STC1") (pin "15") (pinfunction "XTAL2_15") (pintype "passive"))
      (node (ref "Y1") (pin "1") (pinfunction "1_1") (pintype "passive"))
    )
    (net (code "52") (name "GND") (class "Default")
      (node (ref "C1") (pin "2") (pinfunction "2_2") (pintype "passive"))
      (node (ref "C2") (pin "1") (pinfunction "1_1") (pintype "passive"))
      (node (ref "J1") (pin "1") (pinfunction "1_1") (pintype "passive"))
      (node (ref "J2") (pin "1") (pinfunction "1_1") (pintype "passive"))
      (node (ref "POWER_LED1") (pin "2") (pinfunction "K_2") (pintype "passive"))
      (node (ref "R2") (pin "2") (pinfunction "2_2") (pintype "passive"))
      (node (ref "STC1") (pin "17") (pinfunction "GND_17") (pintype "passive"))
      (node (ref "U1") (pin "1") (pinfunction "~{OE}_1") (pintype "input"))
      (node (ref "U1") (pin "10") (pinfunction "GND_10") (pintype "power_in"))
      (node (ref "U2") (pin "1") (pinfunction "~{OE}_1") (pintype "input"))
      (node (ref "U2") (pin "10") (pinfunction "GND_10") (pintype "power_in"))
      (node (ref "U3") (pin "1") (pinfunction "~{OE}_1") (pintype "input"))
      (node (ref "U3") (pin "10") (pinfunction "GND_10") (pintype "power_in"))
      (node (ref "UART1") (pin "1") (pinfunction "1_1") (pintype "passive"))
      (node (ref "USB1") (pin "5") (pinfunction "VSS_5") (pintype "passive"))
    )
    (net (code "53") (name "Net-(POWER1-3*)") (class "Default")
      (node (ref "POWER1") (pin "3") (pinfunction "3*_3") (pintype "passive"))
      (node (ref "USB1") (pin "1") (pinfunction "VCC_1") (pintype "passive"))
    )
    (net (code "54") (name "Net-(POWER_LED1-A)") (class "Default")
      (node (ref "POWER_LED1") (pin "1") (pinfunction "A_1") (pintype "passive"))
      (node (ref "R1") (pin "2") (pinfunction "2_2") (pintype "passive"))
    )
    (net (code "55") (name "VCC") (class "Default")
      (node (ref "C3") (pin "1") (pinfunction "1_1") (pintype "passive"))
      (node (ref "POWER1") (pin "2") (pinfunction "2*_2") (pintype "passive"))
      (node (ref "R1") (pin "1") (pinfunction "1_1") (pintype "passive"))
      (node (ref "RST1") (pin "1") (pinfunction "1_1") (pintype "passive"))
      (node (ref "STC1") (pin "41") (pinfunction "VCC_41") (pintype "passive"))
      (node (ref "U1") (pin "11") (pinfunction "LE_11") (pintype "input"))
      (node (ref "U1") (pin "20") (pinfunction "VCC_20") (pintype "power_in"))
      (node (ref "U2") (pin "11") (pinfunction "LE_11") (pintype "input"))
      (node (ref "U2") (pin "20") (pinfunction "VCC_20") (pintype "power_in"))
      (node (ref "U3") (pin "11") (pinfunction "LE_11") (pintype "input"))
      (node (ref "U3") (pin "20") (pinfunction "VCC_20") (pintype "power_in"))
      (node (ref "UART1") (pin "4") (pinfunction "4_4") (pintype "passive"))
    )
    (net (code "56") (name "unconnected-(POWER1-Pad1)") (class "Default")
      (node (ref "POWER1") (pin "1") (pinfunction "1_1") (pintype "passive"))
    )
    (net (code "57") (name "unconnected-(POWER1-Pad4)") (class "Default")
      (node (ref "POWER1") (pin "4") (pinfunction "4_4") (pintype "passive"))
    )
    (net (code "58") (name "unconnected-(POWER1-Pad5)") (class "Default")
      (node (ref "POWER1") (pin "5") (pinfunction "5_5") (pintype "passive"))
    )
    (net (code "59") (name "unconnected-(POWER1-Pad6)") (class "Default")
      (node (ref "POWER1") (pin "6") (pinfunction "6_6") (pintype "passive"))
    )
    (net (code "60") (name "unconnected-(STC1-ALE{slash}P4.5-Pad30)") (class "Default")
      (node (ref "STC1") (pin "30") (pinfunction "ALE/P4.5_30") (pintype "passive"))
    )
    (net (code "61") (name "unconnected-(STC1-EX_LVD{slash}P4.6{slash}RST2-Pad32)") (class "Default")
      (node (ref "STC1") (pin "32") (pinfunction "EX_LVD/P4.6/RST2_32") (pintype "passive"))
    )
    (net (code "62") (name "unconnected-(STC1-MISO{slash}ADC6{slash}P1.6-Pad3)") (class "Default")
      (node (ref "STC1") (pin "3") (pinfunction "MISO/ADC6/P1.6_3") (pintype "passive"))
    )
    (net (code "63") (name "unconnected-(STC1-MISO{slash}RXD2{slash}CCP0{slash}P4.2-Pad42)") (class "Default")
      (node (ref "STC1") (pin "42") (pinfunction "MISO/RXD2/CCP0/P4.2_42") (pintype "passive"))
    )
    (net (code "64") (name "unconnected-(STC1-MOSI{slash}ADC5{slash}P1.5-Pad2)") (class "Default")
      (node (ref "STC1") (pin "2") (pinfunction "MOSI/ADC5/P1.5_2") (pintype "passive"))
    )
    (net (code "65") (name "unconnected-(STC1-NA{slash}P4.4-Pad29)") (class "Default")
      (node (ref "STC1") (pin "29") (pinfunction "NA/P4.4_29") (pintype "passive"))
    )
    (net (code "66") (name "unconnected-(STC1-P2.7{slash}A15-Pad28)") (class "Default")
      (node (ref "STC1") (pin "28") (pinfunction "P2.7/A15_28") (pintype "passive"))
    )
    (net (code "67") (name "unconnected-(STC1-P4.0{slash}SS-Pad18)") (class "Default")
      (node (ref "STC1") (pin "18") (pinfunction "P4.0/SS_18") (pintype "passive"))
    )
    (net (code "68") (name "unconnected-(STC1-P4.1{slash}ECI{slash}MOSI-Pad31)") (class "Default")
      (node (ref "STC1") (pin "31") (pinfunction "P4.1/ECI/MOSI_31") (pintype "passive"))
    )
    (net (code "69") (name "unconnected-(STC1-P5.0-Pad24)") (class "Default")
      (node (ref "STC1") (pin "24") (pinfunction "P5.0_24") (pintype "passive"))
    )
    (net (code "70") (name "unconnected-(STC1-P5.1-Pad25)") (class "Default")
      (node (ref "STC1") (pin "25") (pinfunction "P5.1_25") (pintype "passive"))
    )
    (net (code "71") (name "unconnected-(STC1-P5.2-Pad48)") (class "Default")
      (node (ref "STC1") (pin "48") (pinfunction "P5.2_48") (pintype "passive"))
    )
    (net (code "72") (name "unconnected-(STC1-P5.3-Pad1)") (class "Default")
      (node (ref "STC1") (pin "1") (pinfunction "P5.3_1") (pintype "passive"))
    )
    (net (code "73") (name "unconnected-(STC1-RxD2{slash}ECI{slash}ADC2{slash}P1.2-Pad45)") (class "Default")
      (node (ref "STC1") (pin "45") (pinfunction "RxD2/ECI/ADC2/P1.2_45") (pintype "passive"))
    )
    (net (code "74") (name "unconnected-(STC1-SCLK{slash}ADC7{slash}P1.7-Pad4)") (class "Default")
      (node (ref "STC1") (pin "4") (pinfunction "SCLK/ADC7/P1.7_4") (pintype "passive"))
    )
    (net (code "75") (name "unconnected-(STC1-SCLK{slash}TXD2{slash}CCP1{slash}P4.3-Pad7)") (class "Default")
      (node (ref "STC1") (pin "7") (pinfunction "SCLK/TXD2/CCP1/P4.3_7") (pintype "passive"))
    )
    (net (code "76") (name "unconnected-(STC1-SS{slash}CCP1{slash}ADC4{slash}P1.4-Pad47)") (class "Default")
      (node (ref "STC1") (pin "47") (pinfunction "SS/CCP1/ADC4/P1.4_47") (pintype "passive"))
    )
    (net (code "77") (name "unconnected-(STC1-TxD2{slash}CCP0{slash}ADC3{slash}P1.3-Pad46)") (class "Default")
      (node (ref "STC1") (pin "46") (pinfunction "TxD2/CCP0/ADC3/P1.3_46") (pintype "passive"))
    )
    (net (code "78") (name "unconnected-(U2-D1-Pad2)") (class "Default")
      (node (ref "U2") (pin "2") (pinfunction "D1_2") (pintype "input"))
    )
    (net (code "79") (name "unconnected-(U2-Q1-Pad19)") (class "Default")
      (node (ref "U2") (pin "19") (pinfunction "Q1_19") (pintype "tri_state"))
    )
    (net (code "80") (name "unconnected-(USB1-D+-Pad3)") (class "Default")
      (node (ref "USB1") (pin "3") (pinfunction "D+_3") (pintype "passive"))
    )
    (net (code "81") (name "unconnected-(USB1-D--Pad2)") (class "Default")
      (node (ref "USB1") (pin "2") (pinfunction "D-_2") (pintype "passive"))
    )
    (net (code "82") (name "unconnected-(USB1-ID-Pad4)") (class "Default")
      (node (ref "USB1") (pin "4") (pinfunction "ID_4") (pintype "passive"))
    )
  )
)
